# Peripherals.net
KiCad netlist of a schematic drawn in Altium Designer
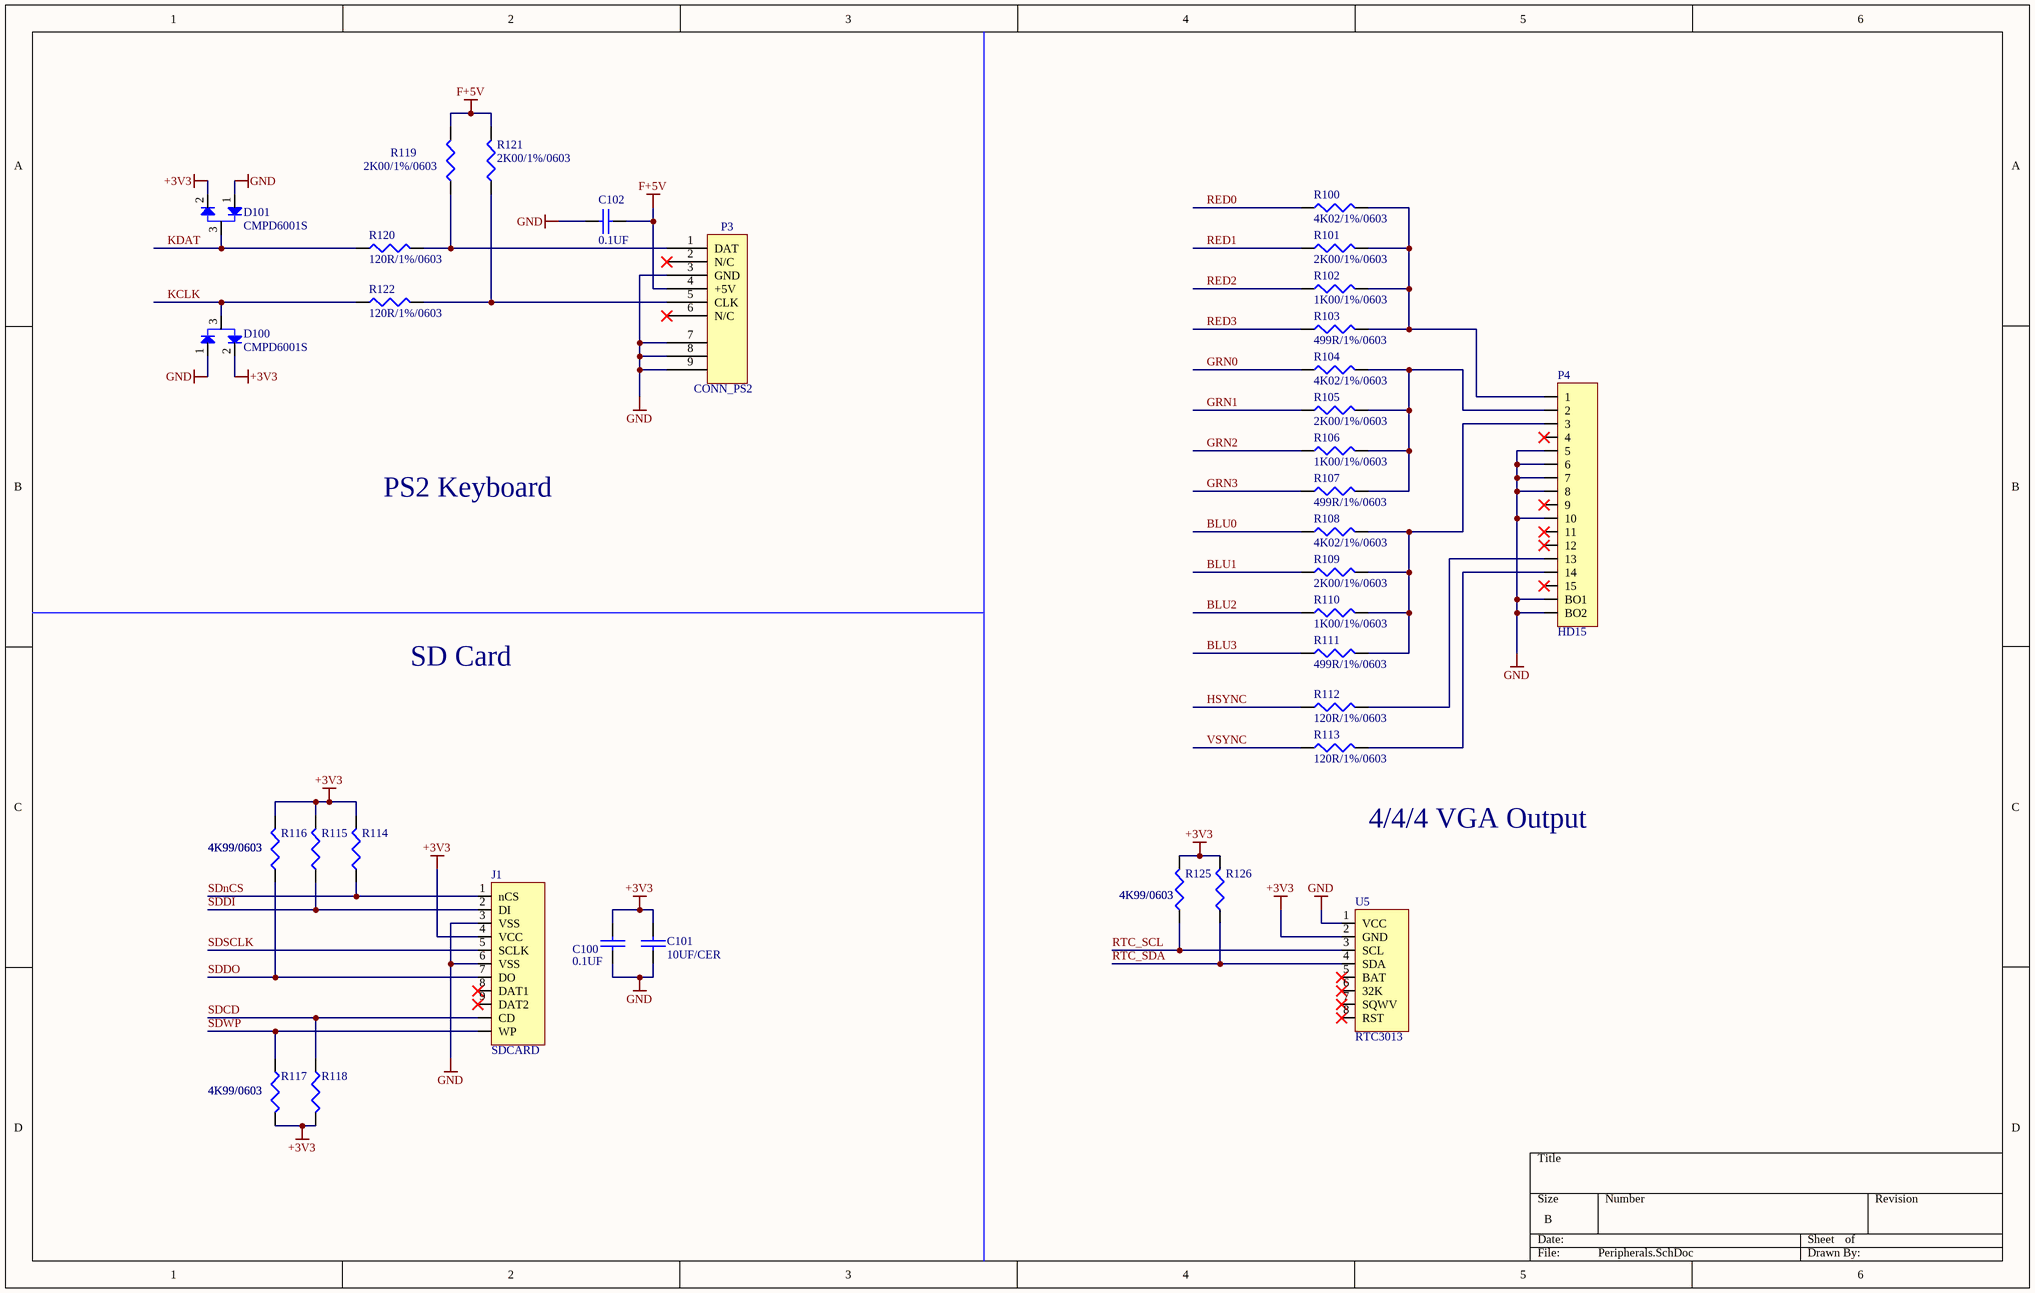
[diagram p0: Peripherals.SchDoc]

(export (version "E")
  (design (tool "Eeschema 10.0.6"))
  (components
    (comp (ref "C100")
      (value "0.1UF")
      (footprint "0603")
      (description "CAP .10UF 16V CERAMIC X7R 0603")
      (libsource (lib "*") (part "0.1UF"))
    )
    (comp (ref "C101")
      (value "10UF/CER")
      (footprint "0805")
      (description "10µF ±10% 25V Ceramic Capacitor X7S 0805")
      (libsource (lib "*") (part "10UF/CER"))
    )
    (comp (ref "C102")
      (value "0.1UF")
      (footprint "0603")
      (description "CAP .10UF 16V CERAMIC X7R 0603")
      (fields (field (name "MFG") "Kemet"))
      (libsource (lib "C64Interface") (part "0.1UF"))
    )
    (comp (ref "D100")
      (value "CMPD6001S")
      (footprint "SOT-23")
      (description "Diode Array 1 Pair Series Connection Standard 75V 250mA Surface Mount TO-236-3, SC-59, SOT-23-3")
      (fields (field (name "MFG") "Central Semiconductor"))
      (libsource (lib "C64Interface") (part "CMPD6001S"))
    )
    (comp (ref "D101")
      (value "CMPD6001S")
      (footprint "SOT-23")
      (description "Diode Array 1 Pair Series Connection Standard 75V 250mA Surface Mount TO-236-3, SC-59, SOT-23-3")
      (fields (field (name "MFG") "Central Semiconductor"))
      (libsource (lib "C64Interface") (part "CMPD6001S"))
    )
    (comp (ref "J1")
      (value "SDCARD")
      (footprint "SDCARD2041021")
      (description "11 (9 + 2) Position Card Connector Secure Digital - SD Surface Mount, Right Angle Gold")
      (fields (field (name "MFG") "TE"))
      (libsource (lib "C64Interface") (part "SDCARD"))
    )
    (comp (ref "P3")
      (value "CONN_PS2")
      (footprint "PS2")
      (description "6 Position Circular Connector Receptacle, Female Sockets Solder Silver")
      (fields (field (name "MFG") "CUI"))
      (libsource (lib "*") (part "CONN_PS2"))
    )
    (comp (ref "P4")
      (value "HD15")
      (footprint "DB15FLC")
      (description "CONN DSUB HD RCPT 15POS R/A SLDR")
      (libsource (lib "*") (part "HD15"))
    )
    (comp (ref "R100")
      (value "4K02/1%/0603")
      (footprint "0603")
      (description "4.02 kOhms ±1% 0.1W, 1/10W Chip Resistor 0603 (1608 Metric) Moisture Resistant Thick Film")
      (fields (field (name "MFG") "Yeago"))
      (libsource (lib "C64Interface") (part "4K02/1%/0603"))
    )
    (comp (ref "R101")
      (value "2K00/1%/0603")
      (footprint "0603")
      (description "2 kOhms ±1% 0.1W, 1/10W Chip Resistor 0603 (1608 Metric) Moisture Resistant Thick Film")
      (fields (field (name "MFG") "Yeago"))
      (libsource (lib "C64Interface") (part "2K00/1%/0603"))
    )
    (comp (ref "R102")
      (value "1K00/1%/0603")
      (footprint "0603")
      (description "1 kOhms ±1% 0.1W, 1/10W Chip Resistor 0603 (1608 Metric) Moisture Resistant Thick Film")
      (fields (field (name "MFG") "Yeago"))
      (libsource (lib "C64Interface") (part "1K00/1%/0603"))
    )
    (comp (ref "R103")
      (value "499R/1%/0603")
      (footprint "0603")
      (description "499 Ohms ±1% 0.1W, 1/10W Chip Resistor 0603 (1608 Metric) Moisture Resistant Thick Film")
      (fields (field (name "MFG") "Yeago"))
      (libsource (lib "C64Interface") (part "499R/1%/0603"))
    )
    (comp (ref "R104")
      (value "4K02/1%/0603")
      (footprint "0603")
      (description "4.02 kOhms ±1% 0.1W, 1/10W Chip Resistor 0603 (1608 Metric) Moisture Resistant Thick Film")
      (fields (field (name "MFG") "Yeago"))
      (libsource (lib "C64Interface") (part "4K02/1%/0603"))
    )
    (comp (ref "R105")
      (value "2K00/1%/0603")
      (footprint "0603")
      (description "2 kOhms ±1% 0.1W, 1/10W Chip Resistor 0603 (1608 Metric) Moisture Resistant Thick Film")
      (fields (field (name "MFG") "Yeago"))
      (libsource (lib "C64Interface") (part "2K00/1%/0603"))
    )
    (comp (ref "R106")
      (value "1K00/1%/0603")
      (footprint "0603")
      (description "1 kOhms ±1% 0.1W, 1/10W Chip Resistor 0603 (1608 Metric) Moisture Resistant Thick Film")
      (fields (field (name "MFG") "Yeago"))
      (libsource (lib "C64Interface") (part "1K00/1%/0603"))
    )
    (comp (ref "R107")
      (value "499R/1%/0603")
      (footprint "0603")
      (description "499 Ohms ±1% 0.1W, 1/10W Chip Resistor 0603 (1608 Metric) Moisture Resistant Thick Film")
      (fields (field (name "MFG") "Yeago"))
      (libsource (lib "C64Interface") (part "499R/1%/0603"))
    )
    (comp (ref "R108")
      (value "4K02/1%/0603")
      (footprint "0603")
      (description "4.02 kOhms ±1% 0.1W, 1/10W Chip Resistor 0603 (1608 Metric) Moisture Resistant Thick Film")
      (fields (field (name "MFG") "Yeago"))
      (libsource (lib "C64Interface") (part "4K02/1%/0603"))
    )
    (comp (ref "R109")
      (value "2K00/1%/0603")
      (footprint "0603")
      (description "2 kOhms ±1% 0.1W, 1/10W Chip Resistor 0603 (1608 Metric) Moisture Resistant Thick Film")
      (fields (field (name "MFG") "Yeago"))
      (libsource (lib "C64Interface") (part "2K00/1%/0603"))
    )
    (comp (ref "R110")
      (value "1K00/1%/0603")
      (footprint "0603")
      (description "1 kOhms ±1% 0.1W, 1/10W Chip Resistor 0603 (1608 Metric) Moisture Resistant Thick Film")
      (fields (field (name "MFG") "Yeago"))
      (libsource (lib "C64Interface") (part "1K00/1%/0603"))
    )
    (comp (ref "R111")
      (value "499R/1%/0603")
      (footprint "0603")
      (description "499 Ohms ±1% 0.1W, 1/10W Chip Resistor 0603 (1608 Metric) Moisture Resistant Thick Film")
      (fields (field (name "MFG") "Yeago"))
      (libsource (lib "C64Interface") (part "499R/1%/0603"))
    )
    (comp (ref "R112")
      (value "120R/1%/0603")
      (footprint "0603")
      (description "120 Ohms ±1% 0.1W, 1/10W Chip Resistor 0603 (1608 Metric) Moisture Resistant Thick Film")
      (fields (field (name "MFG") "Yaego"))
      (libsource (lib "C64Interface") (part "120R/1%/0603"))
    )
    (comp (ref "R113")
      (value "120R/1%/0603")
      (footprint "0603")
      (description "120 Ohms ±1% 0.1W, 1/10W Chip Resistor 0603 (1608 Metric) Moisture Resistant Thick Film")
      (fields (field (name "MFG") "Yaego"))
      (libsource (lib "C64Interface") (part "120R/1%/0603"))
    )
    (comp (ref "R114")
      (value "4K99/0603")
      (footprint "0603")
      (description "RES 4.99K OHM 1/10W 1% 0603 SMD")
      (fields (field (name "MFG") "Dale/Vishay"))
      (libsource (lib "C64Interface") (part "4K99/0603"))
    )
    (comp (ref "R115")
      (value "4K99/0603")
      (footprint "0603")
      (description "RES 4.99K OHM 1/10W 1% 0603 SMD")
      (fields (field (name "MFG") "Dale/Vishay"))
      (libsource (lib "C64Interface") (part "4K99/0603"))
    )
    (comp (ref "R116")
      (value "4K99/0603")
      (footprint "0603")
      (description "RES 4.99K OHM 1/10W 1% 0603 SMD")
      (fields (field (name "MFG") "Dale/Vishay"))
      (libsource (lib "C64Interface") (part "4K99/0603"))
    )
    (comp (ref "R117")
      (value "4K99/0603")
      (footprint "0603")
      (description "RES 4.99K OHM 1/10W 1% 0603 SMD")
      (fields (field (name "MFG") "Dale/Vishay"))
      (libsource (lib "C64Interface") (part "4K99/0603"))
    )
    (comp (ref "R118")
      (value "4K99/0603")
      (footprint "0603")
      (description "RES 4.99K OHM 1/10W 1% 0603 SMD")
      (fields (field (name "MFG") "Dale/Vishay"))
      (libsource (lib "C64Interface") (part "4K99/0603"))
    )
    (comp (ref "R119")
      (value "2K00/1%/0603")
      (footprint "0603")
      (description "2 kOhms ±1% 0.1W, 1/10W Chip Resistor 0603 (1608 Metric) Moisture Resistant Thick Film")
      (fields (field (name "MFG") "Yeago"))
      (libsource (lib "C64Interface") (part "2K00/1%/0603"))
    )
    (comp (ref "R120")
      (value "120R/1%/0603")
      (footprint "0603")
      (description "120 Ohms ±1% 0.1W, 1/10W Chip Resistor 0603 (1608 Metric) Moisture Resistant Thick Film")
      (fields (field (name "MFG") "Yaego"))
      (libsource (lib "C64Interface") (part "120R/1%/0603"))
    )
    (comp (ref "R121")
      (value "2K00/1%/0603")
      (footprint "0603")
      (description "2 kOhms ±1% 0.1W, 1/10W Chip Resistor 0603 (1608 Metric) Moisture Resistant Thick Film")
      (fields (field (name "MFG") "Yeago"))
      (libsource (lib "C64Interface") (part "2K00/1%/0603"))
    )
    (comp (ref "R122")
      (value "120R/1%/0603")
      (footprint "0603")
      (description "120 Ohms ±1% 0.1W, 1/10W Chip Resistor 0603 (1608 Metric) Moisture Resistant Thick Film")
      (fields (field (name "MFG") "Yaego"))
      (libsource (lib "C64Interface") (part "120R/1%/0603"))
    )
    (comp (ref "R125")
      (value "4K99/0603")
      (footprint "0603")
      (description "RES 4.99K OHM 1/10W 1% 0603 SMD")
      (fields (field (name "MFG") "Dale/Vishay"))
      (libsource (lib "C64Interface") (part "4K99/0603"))
    )
    (comp (ref "R126")
      (value "4K99/0603")
      (footprint "0603")
      (description "RES 4.99K OHM 1/10W 1% 0603 SMD")
      (fields (field (name "MFG") "Dale/Vishay"))
      (libsource (lib "C64Interface") (part "4K99/0603"))
    )
    (comp (ref "U5")
      (value "RTC3013")
      (footprint "RTC3013")
      (description "DS3231 Real Time Clock (RTC) Timing Evaluation Board")
      (fields (field (name "MFG") "AdaFruit"))
      (libsource (lib "C64Interface") (part "RTC3013"))
    )
  )
  (nets
    (net (code "1") (name "+3V3") (class "Default")
      (node (ref "C100") (pin "1") (pintype "passive"))
      (node (ref "C101") (pin "2") (pintype "passive"))
      (node (ref "D100") (pin "2") (pintype "passive"))
      (node (ref "D101") (pin "2") (pintype "passive"))
      (node (ref "J1") (pin "4") (pinfunction "VCC_4") (pintype "passive"))
      (node (ref "R114") (pin "2") (pintype "passive"))
      (node (ref "R115") (pin "2") (pintype "passive"))
      (node (ref "R116") (pin "2") (pintype "passive"))
      (node (ref "R117") (pin "2") (pintype "passive"))
      (node (ref "R118") (pin "2") (pintype "passive"))
      (node (ref "R125") (pin "2") (pintype "passive"))
      (node (ref "R126") (pin "2") (pintype "passive"))
      (node (ref "U5") (pin "2") (pinfunction "GND_2") (pintype "passive"))
    )
    (net (code "2") (name "/BLU0") (class "Default") (node (ref "R108") (pin "1") (pintype "passive")))
    (net (code "3") (name "/BLU1") (class "Default") (node (ref "R109") (pin "1") (pintype "passive")))
    (net (code "4") (name "/BLU2") (class "Default") (node (ref "R110") (pin "1") (pintype "passive")))
    (net (code "5") (name "/BLU3") (class "Default") (node (ref "R111") (pin "1") (pintype "passive")))
    (net (code "6") (name "/GRN0") (class "Default") (node (ref "R104") (pin "1") (pintype "passive")))
    (net (code "7") (name "/GRN1") (class "Default") (node (ref "R105") (pin "1") (pintype "passive")))
    (net (code "8") (name "/GRN2") (class "Default") (node (ref "R106") (pin "1") (pintype "passive")))
    (net (code "9") (name "/GRN3") (class "Default") (node (ref "R107") (pin "1") (pintype "passive")))
    (net (code "10") (name "/HSYNC") (class "Default") (node (ref "R112") (pin "1") (pintype "passive")))
    (net (code "11") (name "/KCLK") (class "Default")
      (node (ref "D100") (pin "3") (pintype "passive"))
      (node (ref "R122") (pin "1") (pintype "passive"))
    )
    (net (code "12") (name "/KDAT") (class "Default")
      (node (ref "D101") (pin "3") (pintype "passive"))
      (node (ref "R120") (pin "1") (pintype "passive"))
    )
    (net (code "13") (name "/RED0") (class "Default") (node (ref "R100") (pin "1") (pintype "passive")))
    (net (code "14") (name "/RED1") (class "Default") (node (ref "R101") (pin "1") (pintype "passive")))
    (net (code "15") (name "/RED2") (class "Default") (node (ref "R102") (pin "1") (pintype "passive")))
    (net (code "16") (name "/RED3") (class "Default") (node (ref "R103") (pin "1") (pintype "passive")))
    (net (code "17") (name "/RTC_SCL") (class "Default")
      (node (ref "R125") (pin "1") (pintype "passive"))
      (node (ref "U5") (pin "3") (pinfunction "SCL_3") (pintype "passive"))
    )
    (net (code "18") (name "/RTC_SDA") (class "Default")
      (node (ref "R126") (pin "1") (pintype "passive"))
      (node (ref "U5") (pin "4") (pinfunction "SDA_4") (pintype "passive"))
    )
    (net (code "19") (name "/SDCD") (class "Default")
      (node (ref "J1") (pin "CD") (pinfunction "CD_CD") (pintype "passive"))
      (node (ref "R118") (pin "1") (pintype "passive"))
    )
    (net (code "20") (name "/SDDI") (class "Default")
      (node (ref "J1") (pin "2") (pinfunction "DI_2") (pintype "passive"))
      (node (ref "R115") (pin "1") (pintype "passive"))
    )
    (net (code "21") (name "/SDDO") (class "Default")
      (node (ref "J1") (pin "7") (pinfunction "DO_7") (pintype "passive"))
      (node (ref "R116") (pin "1") (pintype "passive"))
    )
    (net (code "22") (name "/SDSCLK") (class "Default")
      (node (ref "J1") (pin "5") (pinfunction "SCLK_5") (pintype "passive"))
    )
    (net (code "23") (name "/SDWP") (class "Default")
      (node (ref "J1") (pin "WP") (pinfunction "WP_WP") (pintype "passive"))
      (node (ref "R117") (pin "1") (pintype "passive"))
    )
    (net (code "24") (name "/SDnCS") (class "Default")
      (node (ref "J1") (pin "1") (pinfunction "nCS_1") (pintype "passive"))
      (node (ref "R114") (pin "1") (pintype "passive"))
    )
    (net (code "25") (name "/VSYNC") (class "Default") (node (ref "R113") (pin "1") (pintype "passive")))
    (net (code "26") (name "F+5V") (class "Default")
      (node (ref "C102") (pin "2") (pintype "passive"))
      (node (ref "P3") (pin "4") (pinfunction "+5V_4") (pintype "power_in"))
      (node (ref "R119") (pin "2") (pintype "passive"))
      (node (ref "R121") (pin "2") (pintype "passive"))
    )
    (net (code "27") (name "GND") (class "Default")
      (node (ref "C100") (pin "2") (pintype "passive"))
      (node (ref "C101") (pin "1") (pintype "passive"))
      (node (ref "C102") (pin "1") (pintype "passive"))
      (node (ref "D100") (pin "1") (pintype "passive"))
      (node (ref "D101") (pin "1") (pintype "passive"))
      (node (ref "J1") (pin "3") (pinfunction "VSS_3") (pintype "passive"))
      (node (ref "J1") (pin "6") (pinfunction "VSS_6") (pintype "passive"))
      (node (ref "P3") (pin "3") (pinfunction "GND_3") (pintype "power_in"))
      (node (ref "P3") (pin "7") (pintype "power_in"))
      (node (ref "P3") (pin "8") (pintype "power_in"))
      (node (ref "P3") (pin "9") (pintype "power_in"))
      (node (ref "P4") (pin "10") (pinfunction "10_10") (pintype "passive"))
      (node (ref "P4") (pin "5") (pinfunction "5_5") (pintype "passive"))
      (node (ref "P4") (pin "6") (pinfunction "6_6") (pintype "passive"))
      (node (ref "P4") (pin "7") (pinfunction "7_7") (pintype "passive"))
      (node (ref "P4") (pin "8") (pinfunction "8_8") (pintype "passive"))
      (node (ref "P4") (pin "BO1") (pinfunction "BO1_BO1") (pintype "passive"))
      (node (ref "P4") (pin "BO2") (pinfunction "BO2_BO2") (pintype "passive"))
      (node (ref "U5") (pin "1") (pinfunction "VCC_1") (pintype "passive"))
    )
    (net (code "28") (name "Net-(P3-CLK)") (class "Default")
      (node (ref "P3") (pin "5") (pinfunction "CLK_5") (pintype "power_in"))
      (node (ref "R121") (pin "1") (pintype "passive"))
      (node (ref "R122") (pin "2") (pintype "passive"))
    )
    (net (code "29") (name "Net-(P3-DAT)") (class "Default")
      (node (ref "P3") (pin "1") (pinfunction "DAT_1") (pintype "power_in"))
      (node (ref "R119") (pin "1") (pintype "passive"))
      (node (ref "R120") (pin "2") (pintype "passive"))
    )
    (net (code "30") (name "Net-(P4-Pad1)") (class "Default")
      (node (ref "P4") (pin "1") (pinfunction "1_1") (pintype "passive"))
      (node (ref "R100") (pin "2") (pintype "passive"))
      (node (ref "R101") (pin "2") (pintype "passive"))
      (node (ref "R102") (pin "2") (pintype "passive"))
      (node (ref "R103") (pin "2") (pintype "passive"))
    )
    (net (code "31") (name "Net-(P4-Pad2)") (class "Default")
      (node (ref "P4") (pin "2") (pinfunction "2_2") (pintype "passive"))
      (node (ref "R104") (pin "2") (pintype "passive"))
      (node (ref "R105") (pin "2") (pintype "passive"))
      (node (ref "R106") (pin "2") (pintype "passive"))
      (node (ref "R107") (pin "2") (pintype "passive"))
    )
    (net (code "32") (name "Net-(P4-Pad3)") (class "Default")
      (node (ref "P4") (pin "3") (pinfunction "3_3") (pintype "passive"))
      (node (ref "R108") (pin "2") (pintype "passive"))
      (node (ref "R109") (pin "2") (pintype "passive"))
      (node (ref "R110") (pin "2") (pintype "passive"))
      (node (ref "R111") (pin "2") (pintype "passive"))
    )
    (net (code "33") (name "Net-(P4-Pad13)") (class "Default")
      (node (ref "P4") (pin "13") (pinfunction "13_13") (pintype "passive"))
      (node (ref "R112") (pin "2") (pintype "passive"))
    )
    (net (code "34") (name "Net-(P4-Pad14)") (class "Default")
      (node (ref "P4") (pin "14") (pinfunction "14_14") (pintype "passive"))
      (node (ref "R113") (pin "2") (pintype "passive"))
    )
    (net (code "35") (name "unconnected-(J1-DAT1-Pad8)") (class "Default")
      (node (ref "J1") (pin "8") (pinfunction "DAT1_8") (pintype "passive+no_connect"))
    )
    (net (code "36") (name "unconnected-(J1-DAT2-Pad9)") (class "Default")
      (node (ref "J1") (pin "9") (pinfunction "DAT2_9") (pintype "passive+no_connect"))
    )
    (net (code "37") (name "unconnected-(P3-N{slash}C-Pad2)") (class "Default")
      (node (ref "P3") (pin "2") (pinfunction "N/C_2") (pintype "power_in+no_connect"))
    )
    (net (code "38") (name "unconnected-(P3-N{slash}C-Pad6)") (class "Default")
      (node (ref "P3") (pin "6") (pinfunction "N/C_6") (pintype "power_in+no_connect"))
    )
    (net (code "39") (name "unconnected-(P4-Pad4)") (class "Default")
      (node (ref "P4") (pin "4") (pinfunction "4_4") (pintype "passive+no_connect"))
    )
    (net (code "40") (name "unconnected-(P4-Pad9)") (class "Default")
      (node (ref "P4") (pin "9") (pinfunction "9_9") (pintype "passive+no_connect"))
    )
    (net (code "41") (name "unconnected-(P4-Pad11)") (class "Default")
      (node (ref "P4") (pin "11") (pinfunction "11_11") (pintype "passive+no_connect"))
    )
    (net (code "42") (name "unconnected-(P4-Pad12)") (class "Default")
      (node (ref "P4") (pin "12") (pinfunction "12_12") (pintype "passive+no_connect"))
    )
    (net (code "43") (name "unconnected-(P4-Pad15)") (class "Default")
      (node (ref "P4") (pin "15") (pinfunction "15_15") (pintype "passive+no_connect"))
    )
    (net (code "44") (name "unconnected-(U5-32K-Pad6)") (class "Default")
      (node (ref "U5") (pin "6") (pinfunction "32K_6") (pintype "passive+no_connect"))
    )
    (net (code "45") (name "unconnected-(U5-BAT-Pad5)") (class "Default")
      (node (ref "U5") (pin "5") (pinfunction "BAT_5") (pintype "passive+no_connect"))
    )
    (net (code "46") (name "unconnected-(U5-RST-Pad8)") (class "Default")
      (node (ref "U5") (pin "8") (pinfunction "RST_8") (pintype "passive+no_connect"))
    )
    (net (code "47") (name "unconnected-(U5-SQWV-Pad7)") (class "Default")
      (node (ref "U5") (pin "7") (pinfunction "SQWV_7") (pintype "passive+no_connect"))
    )
  )
)
